# decoupling.net
KiCad netlist of a schematic drawn in EAGLE
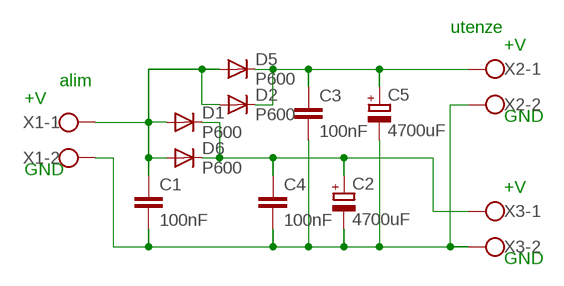
[diagram p0: schematic, sheet 1]

(export (version "E")
  (design (tool "Eeschema 10.0.6"))
  (components
    (comp (ref "C1")
      (value "100nF")
      (footprint "eagle-import:C050-025X075")
      (libsource (lib "eagle-import") (part "C-EU050-025X075"))
    )
    (comp (ref "C2")
      (value "4700uF")
      (footprint "eagle-import:E7,5-16")
      (libsource (lib "eagle-import") (part "CPOL-EUE7.5-16"))
    )
    (comp (ref "C3")
      (value "100nF")
      (footprint "eagle-import:C050-025X075")
      (libsource (lib "eagle-import") (part "C-EU050-025X075"))
    )
    (comp (ref "C4")
      (value "100nF")
      (footprint "eagle-import:C050-025X075")
      (libsource (lib "eagle-import") (part "C-EU050-025X075"))
    )
    (comp (ref "C5")
      (value "4700uF")
      (footprint "eagle-import:E7,5-16")
      (libsource (lib "eagle-import") (part "CPOL-EUE7.5-16"))
    )
    (comp (ref "D1")
      (value "P600")
      (footprint "eagle-import:P6-15")
      (libsource (lib "eagle-import") (part "P600"))
    )
    (comp (ref "D2")
      (value "P600")
      (footprint "eagle-import:P6-15")
      (libsource (lib "eagle-import") (part "P600"))
    )
    (comp (ref "D5")
      (value "P600")
      (footprint "eagle-import:P6-15")
      (libsource (lib "eagle-import") (part "P600"))
    )
    (comp (ref "D6")
      (value "P600")
      (footprint "eagle-import:P6-15")
      (libsource (lib "eagle-import") (part "P600"))
    )
    (comp (ref "X1")
      (value "W237-102")
      (footprint "eagle-import:W237-102")
      (fields (field (name "MPN") "237-102"))
      (libsource (lib "eagle-import") (part "W237-102"))
    )
    (comp (ref "X2")
      (value "W237-102")
      (footprint "eagle-import:W237-102")
      (fields (field (name "MPN") "237-102"))
      (libsource (lib "eagle-import") (part "W237-102"))
    )
    (comp (ref "X3")
      (value "W237-102")
      (footprint "eagle-import:W237-102")
      (fields (field (name "MPN") "237-102"))
      (libsource (lib "eagle-import") (part "W237-102"))
    )
  )
  (nets
    (net (code "1") (name "Net-(X1A-KL)") (class "Default")
      (node (ref "C1") (pin "1") (pinfunction "1_1") (pintype "passive"))
      (node (ref "D1") (pin "A") (pinfunction "A_A") (pintype "passive"))
      (node (ref "D2") (pin "A") (pinfunction "A_A") (pintype "passive"))
      (node (ref "D5") (pin "A") (pinfunction "A_A") (pintype "passive"))
      (node (ref "D6") (pin "A") (pinfunction "A_A") (pintype "passive"))
      (node (ref "X1") (pin "1") (pinfunction "KL_1") (pintype "passive"))
    )
    (net (code "2") (name "Net-(X1B-KL)") (class "Default")
      (node (ref "C1") (pin "2") (pinfunction "2_2") (pintype "passive"))
      (node (ref "C2") (pin "-") (pinfunction "-_-") (pintype "passive"))
      (node (ref "C3") (pin "2") (pinfunction "2_2") (pintype "passive"))
      (node (ref "C4") (pin "2") (pinfunction "2_2") (pintype "passive"))
      (node (ref "C5") (pin "-") (pinfunction "-_-") (pintype "passive"))
      (node (ref "X1") (pin "2") (pinfunction "KL_2") (pintype "passive"))
      (node (ref "X2") (pin "2") (pinfunction "KL_2") (pintype "passive"))
      (node (ref "X3") (pin "2") (pinfunction "KL_2") (pintype "passive"))
    )
    (net (code "3") (name "Net-(X2A-KL)") (class "Default")
      (node (ref "C3") (pin "1") (pinfunction "1_1") (pintype "passive"))
      (node (ref "C5") (pin "+") (pinfunction "+_+") (pintype "passive"))
      (node (ref "D2") (pin "C") (pinfunction "C_C") (pintype "passive"))
      (node (ref "D5") (pin "C") (pinfunction "C_C") (pintype "passive"))
      (node (ref "X2") (pin "1") (pinfunction "KL_1") (pintype "passive"))
    )
    (net (code "4") (name "Net-(X3A-KL)") (class "Default")
      (node (ref "C2") (pin "+") (pinfunction "+_+") (pintype "passive"))
      (node (ref "C4") (pin "1") (pinfunction "1_1") (pintype "passive"))
      (node (ref "D1") (pin "C") (pinfunction "C_C") (pintype "passive"))
      (node (ref "D6") (pin "C") (pinfunction "C_C") (pintype "passive"))
      (node (ref "X3") (pin "1") (pinfunction "KL_1") (pintype "passive"))
    )
  )
)
